# EEPROM.net
KiCad netlist of a schematic drawn in Altium Designer
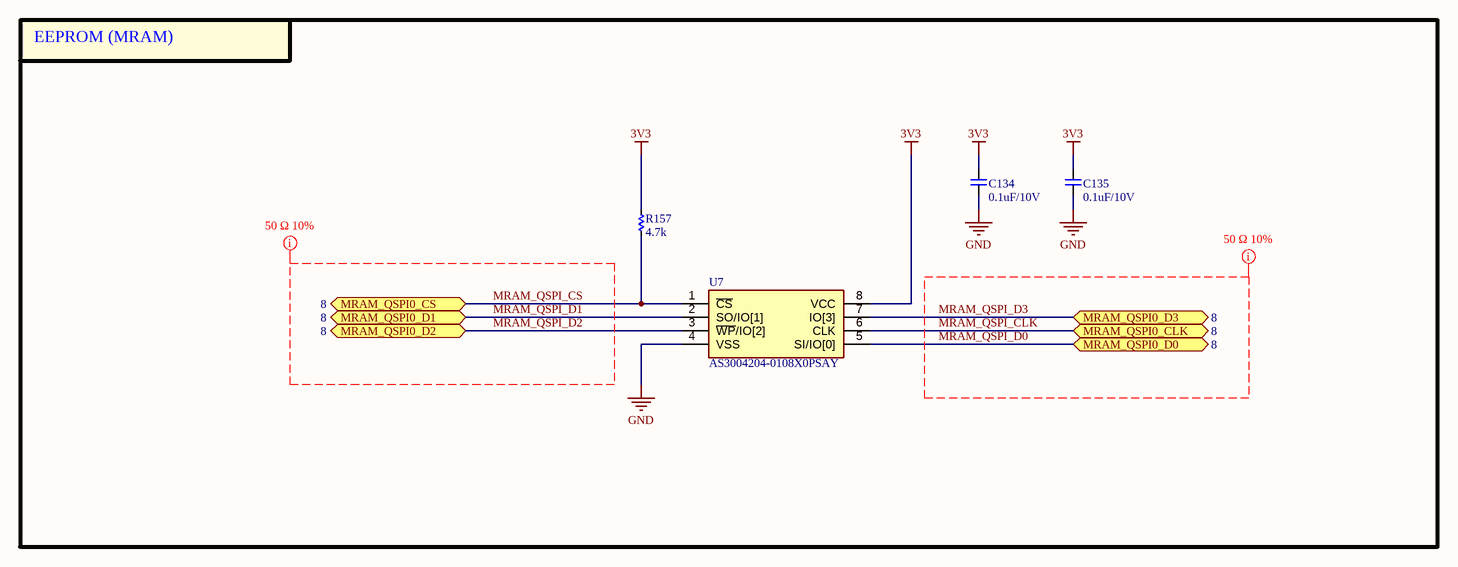
[diagram p0: EEPROM.SchDoc]

(export (version "E")
  (design (tool "Eeschema 10.0.6"))
  (components
    (comp (ref "C134")
      (value "0.1uF/10V")
      (footprint "CAP_C_1005X50_L")
      (description "CAP CHIP")
      (libsource (lib "IFBschelib") (part "_CAP_C_2"))
    )
    (comp (ref "C135")
      (value "0.1uF/10V")
      (footprint "CAP_C_1005X50_L")
      (description "CAP CHIP")
      (libsource (lib "IFBschelib") (part "_CAP_C_2"))
    )
    (comp (ref "R157")
      (value "4.7k")
      (footprint "RES_C_1005x30_L")
      (description "RES")
      (libsource (lib "IFBschelib") (part "_RES_B_2"))
    )
    (comp (ref "U7")
      (value "AS3004204-0108X0PSAY")
      (footprint "SOIC127P790X216-8N")
      (fields (field (name "MOUSER PART NUMBER") "793-30042040108X0PSY"))
      (libsource (lib "IFBschelib") (part "AS3004204-0108X0PSAY"))
    )
  )
  (nets
    (net (code "1") (name "/MRAM_QSPI_CLK") (class "Default")
      (node (ref "U7") (pin "6") (pinfunction "CLK_6") (pintype "passive"))
    )
    (net (code "2") (name "/MRAM_QSPI_CS") (class "Default")
      (node (ref "R157") (pin "2") (pinfunction "2_2") (pintype "passive"))
      (node (ref "U7") (pin "1") (pinfunction "~{CS}_1") (pintype "passive"))
    )
    (net (code "3") (name "/MRAM_QSPI_D0") (class "Default")
      (node (ref "U7") (pin "5") (pinfunction "SI/IO[0]_5") (pintype "passive"))
    )
    (net (code "4") (name "/MRAM_QSPI_D1") (class "Default")
      (node (ref "U7") (pin "2") (pinfunction "SO/IO[1]_2") (pintype "passive"))
    )
    (net (code "5") (name "/MRAM_QSPI_D2") (class "Default")
      (node (ref "U7") (pin "3") (pinfunction "~{WP}/IO[2]_3") (pintype "passive"))
    )
    (net (code "6") (name "/MRAM_QSPI_D3") (class "Default")
      (node (ref "U7") (pin "7") (pinfunction "IO[3]_7") (pintype "passive"))
    )
    (net (code "7") (name "3V3") (class "Default")
      (node (ref "C134") (pin "2") (pinfunction "2_2") (pintype "passive"))
      (node (ref "C135") (pin "2") (pinfunction "2_2") (pintype "passive"))
      (node (ref "R157") (pin "1") (pinfunction "1_1") (pintype "passive"))
      (node (ref "U7") (pin "8") (pinfunction "VCC_8") (pintype "passive"))
    )
    (net (code "8") (name "GND") (class "Default")
      (node (ref "C134") (pin "1") (pinfunction "1_1") (pintype "passive"))
      (node (ref "C135") (pin "1") (pinfunction "1_1") (pintype "passive"))
      (node (ref "U7") (pin "4") (pinfunction "VSS_4") (pintype "passive"))
    )
  )
)
